# power_electronicsV4_1.net
KiCad netlist of a schematic drawn in EAGLE
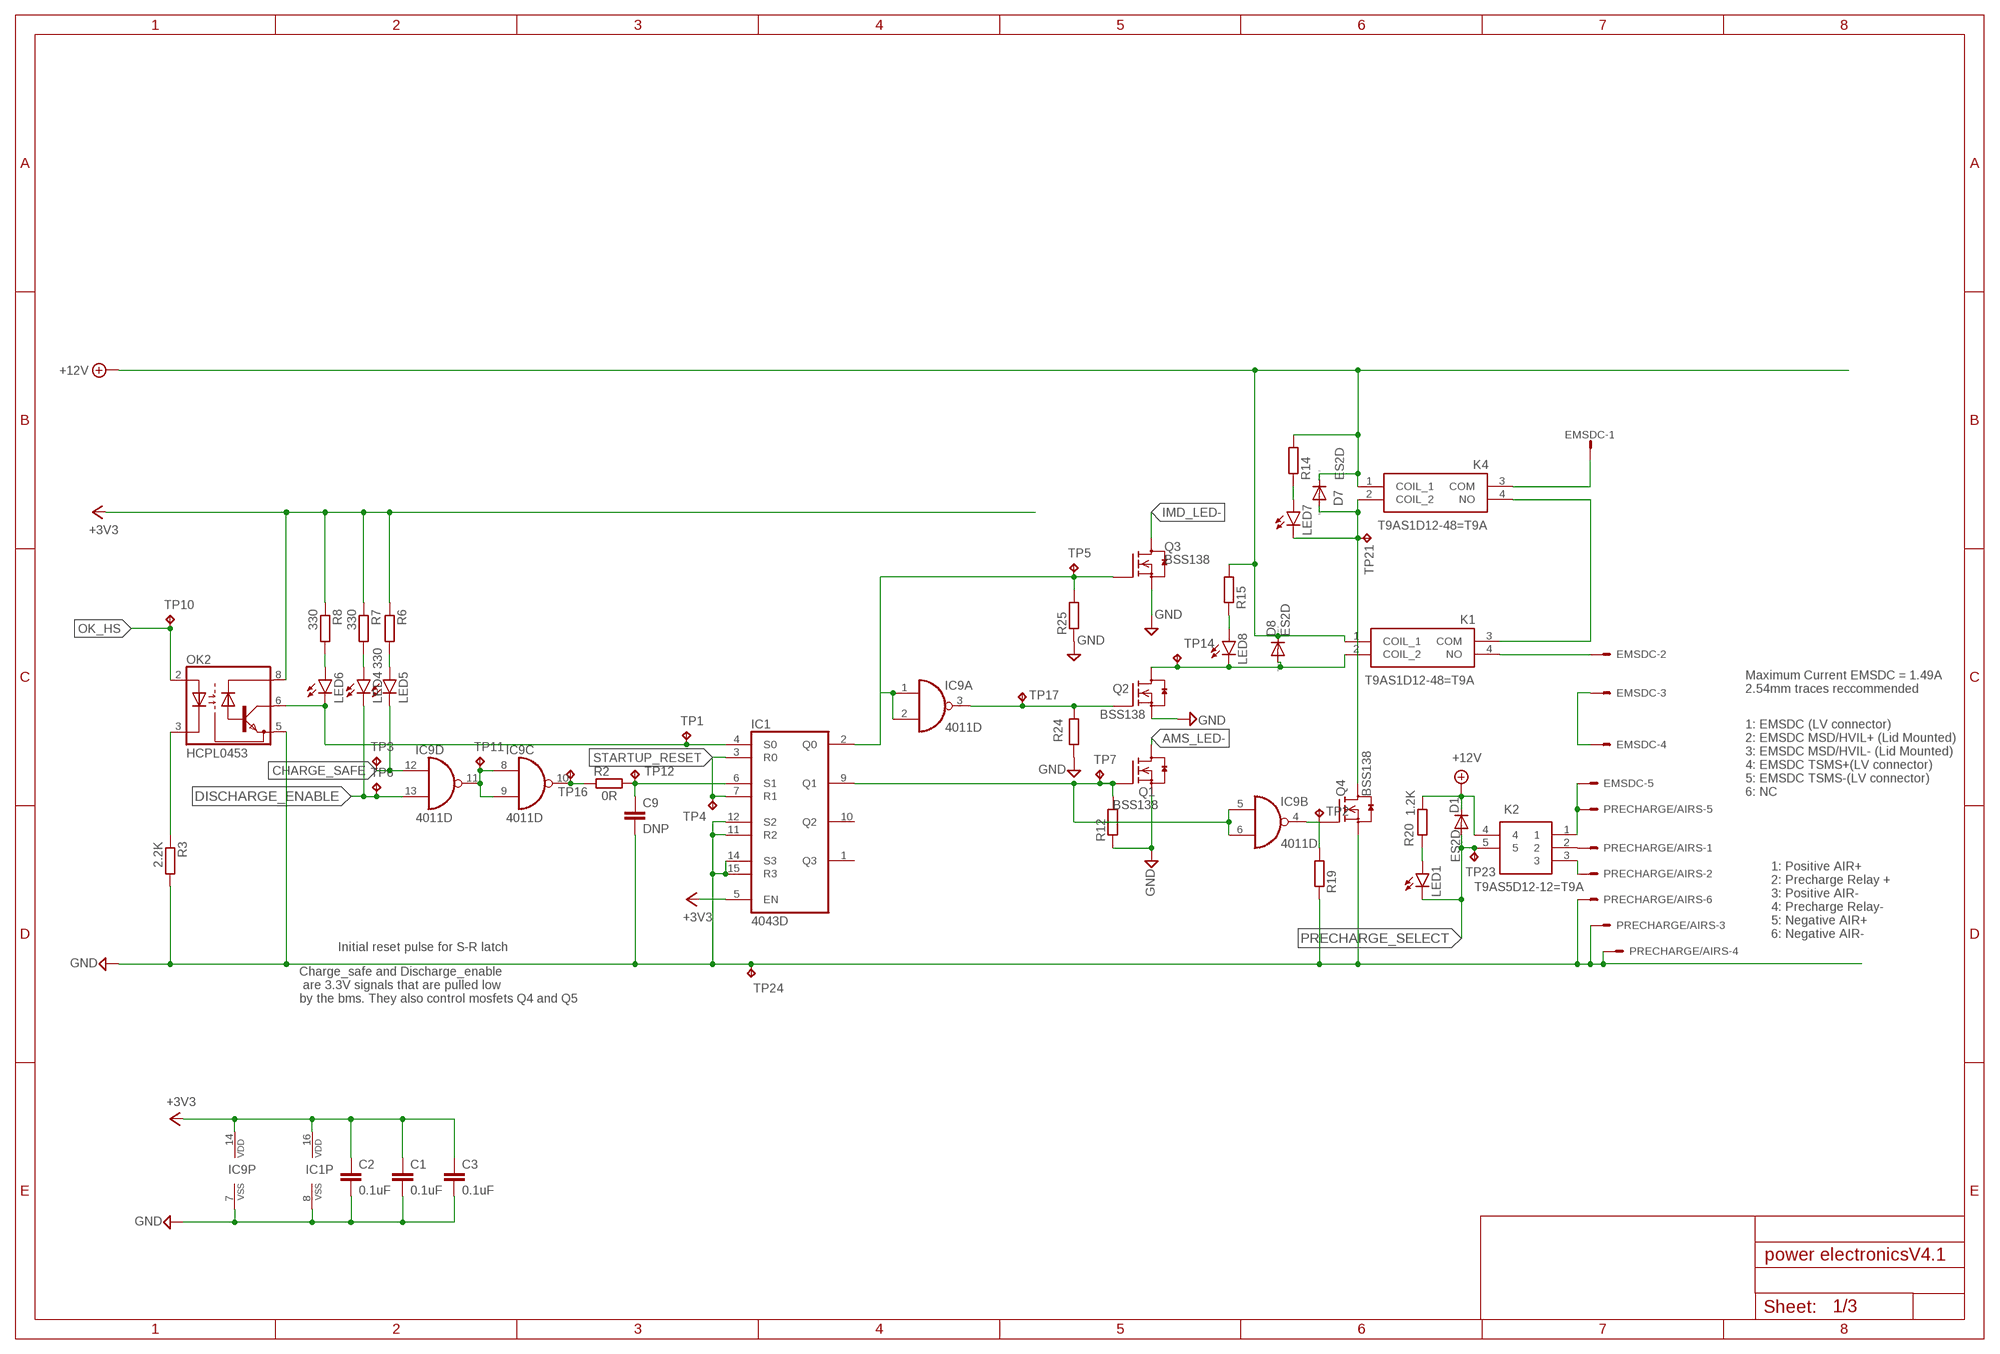
[diagram p0: schematic, sheet 1]
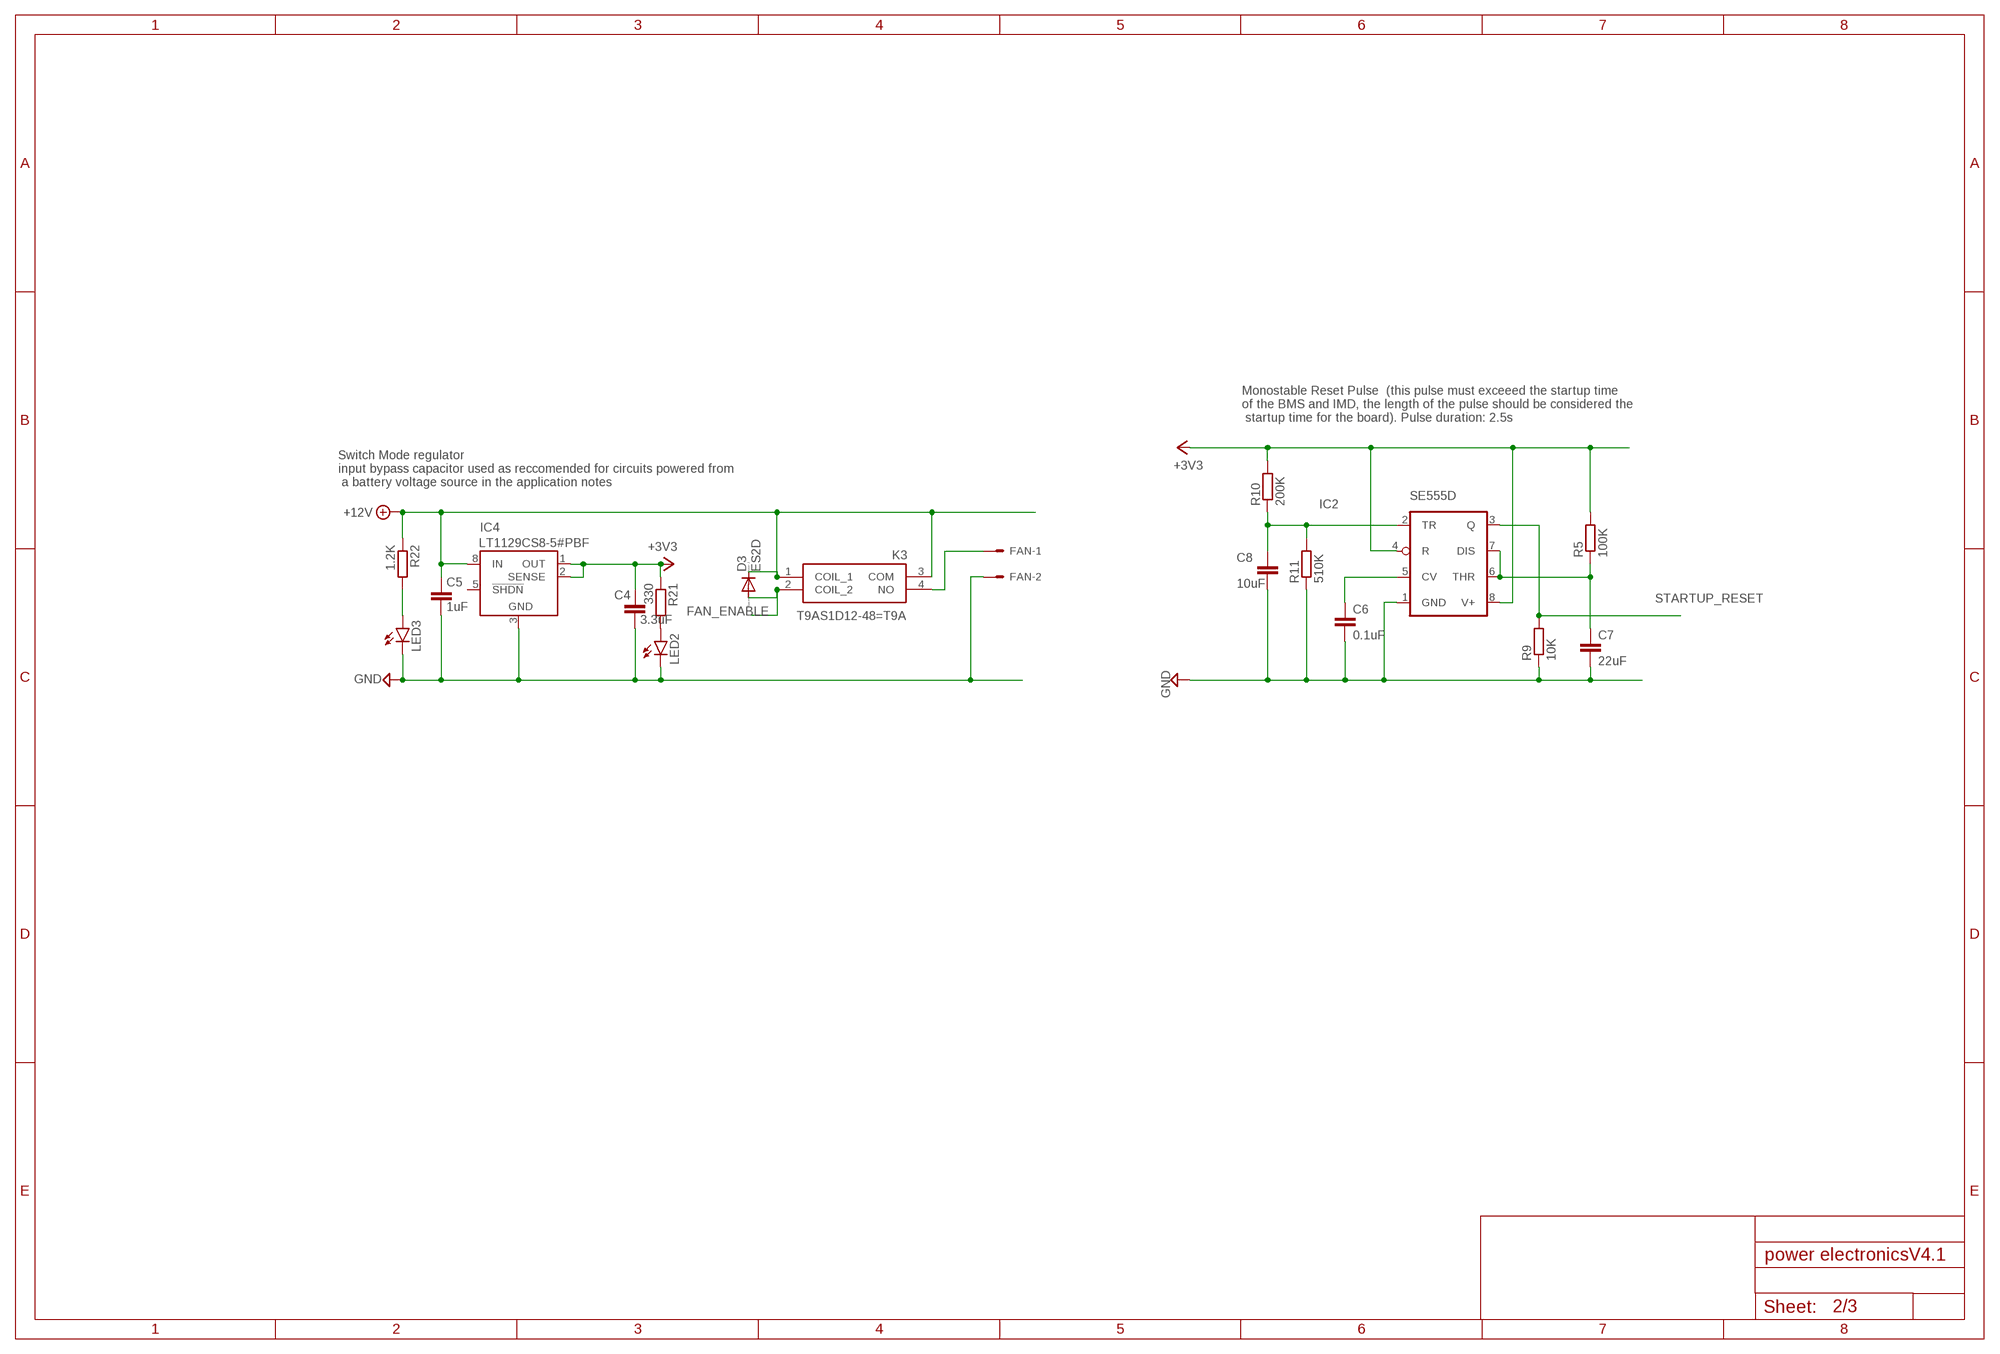
[diagram p1: schematic, sheet 2]
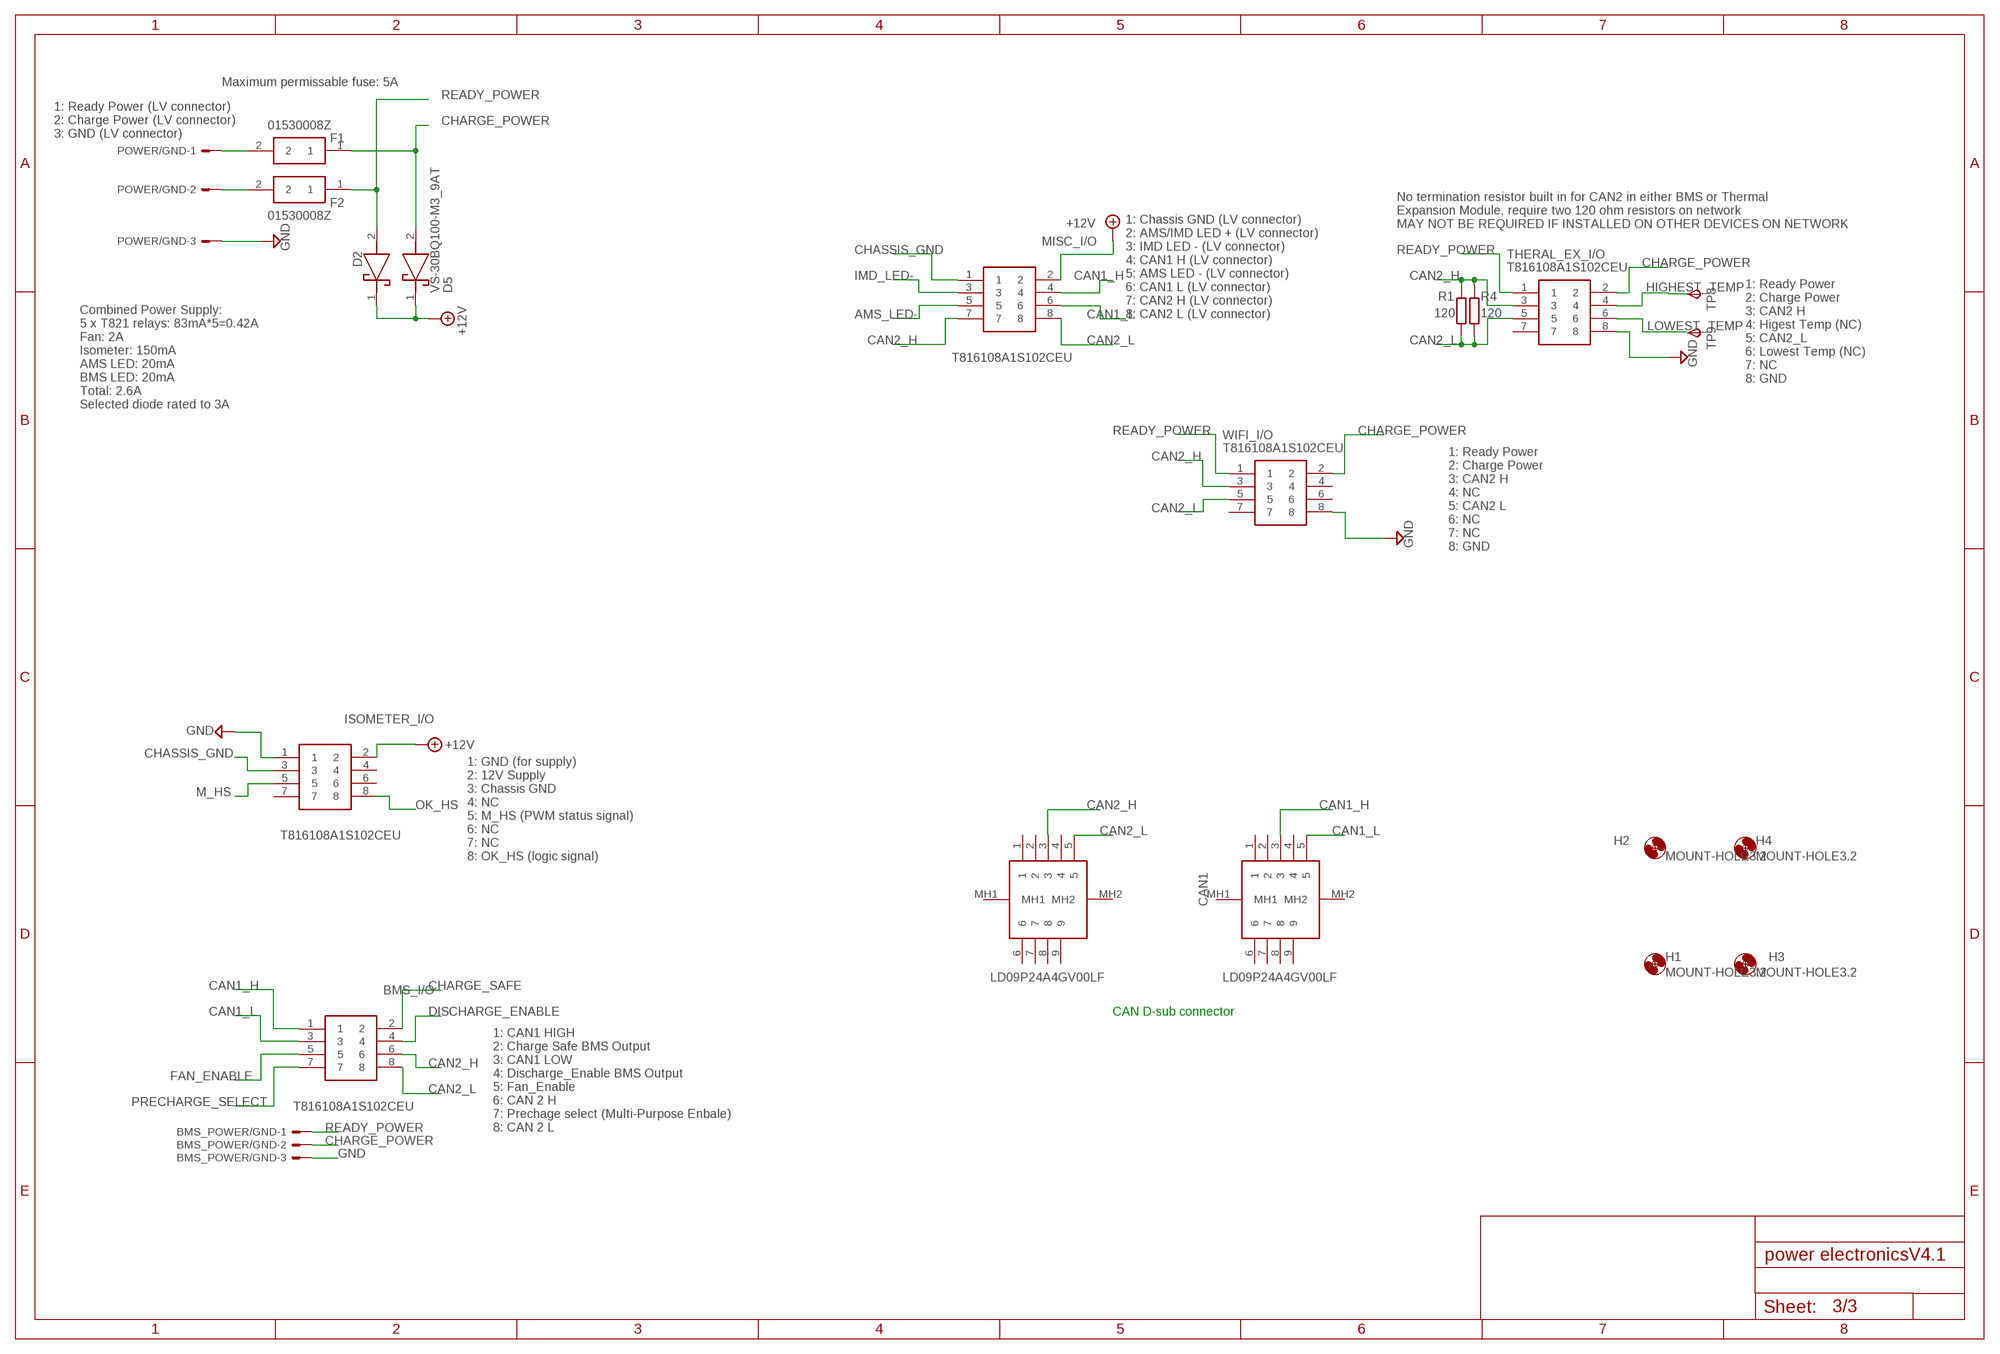
[diagram p2: schematic, sheet 3]

(export (version "E")
  (design (tool "Eeschema 10.0.6"))
  (components
    (comp (ref "C4")
      (value "3.3uF")
      (footprint "eagle-import:C0805")
      (libsource (lib "eagle-import") (part "C-EUC0805"))
    )
    (comp (ref "C5")
      (value "1uF")
      (footprint "eagle-import:C0805")
      (libsource (lib "eagle-import") (part "C-EUC0805"))
    )
    (comp (ref "C6")
      (value "0.1uF")
      (footprint "eagle-import:C0805")
      (libsource (lib "eagle-import") (part "C-EUC0805"))
    )
    (comp (ref "C7")
      (value "22uF")
      (footprint "eagle-import:C1206")
      (libsource (lib "eagle-import") (part "C-EUC1206"))
    )
    (comp (ref "C8")
      (value "10uF")
      (footprint "eagle-import:C0805")
      (libsource (lib "eagle-import") (part "C-EUC0805"))
    )
    (comp (ref "D3")
      (value "ES2D")
      (footprint "eagle-import:SMB")
      (libsource (lib "eagle-import") (part "ES2D"))
    )
    (comp (ref "FAN")
      (value "KK-156-2")
      (footprint "eagle-import:KK-156-2")
      (fields (field (name "MF") "MOLEX"))
      (libsource (lib "eagle-import") (part "KK-156-2"))
    )
    (comp (ref "IC2")
      (value "SE555D")
      (footprint "eagle-import:SO08")
      (libsource (lib "eagle-import") (part "555DSE"))
    )
    (comp (ref "IC4")
      (value "LT1129CS8")
      (footprint "eagle-import:SOIC8")
      (fields (field (name "MPN") "LT1129CS8-5#PBF"))
      (libsource (lib "eagle-import") (part "LT1129CS8"))
    )
    (comp (ref "K3")
      (value "T9AS1D12-48=T9A")
      (footprint "eagle-import:T9AS1D1248T9A")
      (fields (field (name "RS_PART_NUMBER") "6802534P"))
      (libsource (lib "eagle-import") (part "T9AS1D12-48=T9A"))
    )
    (comp (ref "LED2")
      (value "LEDSML0805")
      (footprint "eagle-import:SML0805")
      (libsource (lib "eagle-import") (part "LEDSML0805"))
    )
    (comp (ref "LED3")
      (value "LEDSML0805")
      (footprint "eagle-import:SML0805")
      (libsource (lib "eagle-import") (part "LEDSML0805"))
    )
    (comp (ref "R5")
      (value "100K")
      (footprint "eagle-import:R0805")
      (libsource (lib "eagle-import") (part "R-EU_R0805"))
    )
    (comp (ref "R9")
      (value "10K")
      (footprint "eagle-import:R0805")
      (libsource (lib "eagle-import") (part "R-EU_R0805"))
    )
    (comp (ref "R10")
      (value "200K")
      (footprint "eagle-import:R0805")
      (libsource (lib "eagle-import") (part "R-EU_R0805"))
    )
    (comp (ref "R11")
      (value "510K")
      (footprint "eagle-import:R0805")
      (libsource (lib "eagle-import") (part "R-EU_R0805"))
    )
    (comp (ref "R21")
      (value "330")
      (footprint "eagle-import:R0805")
      (libsource (lib "eagle-import") (part "R-EU_R0805"))
    )
    (comp (ref "R22")
      (value "1.2K")
      (footprint "eagle-import:R0805")
      (libsource (lib "eagle-import") (part "R-EU_R0805"))
    )
    (comp (ref "BMS_I/O")
      (value "T816108A1S102CEU")
      (footprint "eagle-import:T816108A1S102CEU")
      (libsource (lib "eagle-import") (part "T816108A1S102CEU"))
    )
    (comp (ref "BMS_POWER/GND")
      (value "KK-156-3")
      (footprint "eagle-import:KK-156-3")
      (fields (field (name "MF") "MOLEX"))
      (libsource (lib "eagle-import") (part "KK-156-3"))
    )
    (comp (ref "CAN1")
      (value "LD09P24A4GV00LF")
      (footprint "eagle-import:LD09P24A4GV00LF")
      (fields (field (name "MOUSER_PART_NUMBER") "649-LD09P24A4GV00LF"))
      (libsource (lib "eagle-import") (part "LD09P24A4GV00LF"))
    )
    (comp (ref "CAN2")
      (value "LD09P24A4GV00LF")
      (footprint "eagle-import:LD09P24A4GV00LF")
      (fields (field (name "MOUSER_PART_NUMBER") "649-LD09P24A4GV00LF"))
      (libsource (lib "eagle-import") (part "LD09P24A4GV00LF"))
    )
    (comp (ref "D2")
      (value "VS-30BQ100-M3_9AT")
      (footprint "eagle-import:DIOM7959X262N")
      (fields
        (field (name "MANUFACTURER_PART_NUMBER") "VS-30BQ100-M3/9AT")
        (field (name "MOUSER_PART_NUMBER") "78-VS-30BQ100-M39AT")
      )
      (libsource (lib "eagle-import") (part "VS-30BQ100-M3_9AT"))
    )
    (comp (ref "D5")
      (value "VS-30BQ100-M3_9AT")
      (footprint "eagle-import:DIOM7959X262N")
      (fields
        (field (name "MANUFACTURER_PART_NUMBER") "VS-30BQ100-M3/9AT")
        (field (name "MOUSER_PART_NUMBER") "78-VS-30BQ100-M39AT")
      )
      (libsource (lib "eagle-import") (part "VS-30BQ100-M3_9AT"))
    )
    (comp (ref "F1")
      (value "01530008Z")
      (footprint "eagle-import:01530008")
      (fields (field (name "RS_PART_NUMBER") "3607317"))
      (libsource (lib "eagle-import") (part "01530008Z"))
    )
    (comp (ref "F2")
      (value "01530008Z")
      (footprint "eagle-import:01530008")
      (fields (field (name "RS_PART_NUMBER") "3607317"))
      (libsource (lib "eagle-import") (part "01530008Z"))
    )
    (comp (ref "H1")
      (value "MOUNT-HOLE3.2")
      (footprint "eagle-import:3,2")
      (libsource (lib "eagle-import") (part "MOUNT-HOLE3.2"))
    )
    (comp (ref "H2")
      (value "MOUNT-HOLE3.2")
      (footprint "eagle-import:3,2")
      (libsource (lib "eagle-import") (part "MOUNT-HOLE3.2"))
    )
    (comp (ref "H3")
      (value "MOUNT-HOLE3.2")
      (footprint "eagle-import:3,2")
      (libsource (lib "eagle-import") (part "MOUNT-HOLE3.2"))
    )
    (comp (ref "H4")
      (value "MOUNT-HOLE3.2")
      (footprint "eagle-import:3,2")
      (libsource (lib "eagle-import") (part "MOUNT-HOLE3.2"))
    )
    (comp (ref "ISOMETER_I/O")
      (value "T816108A1S102CEU")
      (footprint "eagle-import:T816108A1S102CEU")
      (libsource (lib "eagle-import") (part "T816108A1S102CEU"))
    )
    (comp (ref "MISC_I/O")
      (value "T816108A1S102CEU")
      (footprint "eagle-import:T816108A1S102CEU")
      (libsource (lib "eagle-import") (part "T816108A1S102CEU"))
    )
    (comp (ref "POWER/GND")
      (value "KK-156-3")
      (footprint "eagle-import:KK-156-3")
      (fields (field (name "MF") "MOLEX"))
      (libsource (lib "eagle-import") (part "KK-156-3"))
    )
    (comp (ref "R1")
      (value "120")
      (footprint "eagle-import:R1206")
      (libsource (lib "eagle-import") (part "R-EU_R1206"))
    )
    (comp (ref "R4")
      (value "120")
      (footprint "eagle-import:R1206")
      (libsource (lib "eagle-import") (part "R-EU_R1206"))
    )
    (comp (ref "THERAL_EX_I/O")
      (value "T816108A1S102CEU")
      (footprint "eagle-import:T816108A1S102CEU")
      (libsource (lib "eagle-import") (part "T816108A1S102CEU"))
    )
    (comp (ref "TP8")
      (value "TPSTP11R")
      (footprint "eagle-import:TP11R")
      (libsource (lib "eagle-import") (part "TPSTP11R"))
    )
    (comp (ref "TP9")
      (value "TPSTP11R")
      (footprint "eagle-import:TP11R")
      (libsource (lib "eagle-import") (part "TPSTP11R"))
    )
    (comp (ref "WIFI_I/O")
      (value "T816108A1S102CEU")
      (footprint "eagle-import:T816108A1S102CEU")
      (libsource (lib "eagle-import") (part "T816108A1S102CEU"))
    )
    (comp (ref "C1")
      (value "0.1uF")
      (footprint "eagle-import:C0805")
      (libsource (lib "eagle-import") (part "C-EUC0805"))
    )
    (comp (ref "C2")
      (value "0.1uF")
      (footprint "eagle-import:C0805")
      (libsource (lib "eagle-import") (part "C-EUC0805"))
    )
    (comp (ref "C3")
      (value "0.1uF")
      (footprint "eagle-import:C0805")
      (libsource (lib "eagle-import") (part "C-EUC0805"))
    )
    (comp (ref "C9")
      (value "DNP")
      (footprint "eagle-import:C0805K")
      (libsource (lib "eagle-import") (part "C-EUC0805K"))
    )
    (comp (ref "D1")
      (value "ES2D")
      (footprint "eagle-import:SMB")
      (libsource (lib "eagle-import") (part "ES2D"))
    )
    (comp (ref "D7")
      (value "ES2D")
      (footprint "eagle-import:SMB")
      (libsource (lib "eagle-import") (part "ES2D"))
    )
    (comp (ref "D8")
      (value "ES2D")
      (footprint "eagle-import:SMB")
      (libsource (lib "eagle-import") (part "ES2D"))
    )
    (comp (ref "EMSDC")
      (value "KK-156-6")
      (footprint "eagle-import:KK-156-6")
      (fields (field (name "MF") "MOLEX"))
      (libsource (lib "eagle-import") (part "KK-156-6"))
    )
    (comp (ref "IC1")
      (value "4043D")
      (footprint "eagle-import:SO16")
      (libsource (lib "eagle-import") (part "4043D"))
    )
    (comp (ref "IC9")
      (value "4011D")
      (footprint "eagle-import:SO14")
      (libsource (lib "eagle-import") (part "4011D"))
    )
    (comp (ref "K1")
      (value "T9AS1D12-48=T9A")
      (footprint "eagle-import:T9AS1D1248T9A")
      (fields (field (name "RS_PART_NUMBER") "6802534P"))
      (libsource (lib "eagle-import") (part "T9AS1D12-48=T9A"))
    )
    (comp (ref "K2")
      (value "T9AS5D12-12=T9A")
      (footprint "eagle-import:T9AS1D12")
      (fields (field (name "RS_PART_NUMBER") "6802528"))
      (libsource (lib "eagle-import") (part "T9AS5D12-12=T9A"))
    )
    (comp (ref "K4")
      (value "T9AS1D12-48=T9A")
      (footprint "eagle-import:T9AS1D1248T9A")
      (fields (field (name "RS_PART_NUMBER") "6802534P"))
      (libsource (lib "eagle-import") (part "T9AS1D12-48=T9A"))
    )
    (comp (ref "LED1")
      (value "LEDSML0805")
      (footprint "eagle-import:SML0805")
      (libsource (lib "eagle-import") (part "LEDSML0805"))
    )
    (comp (ref "LED4")
      (value "LEDSML0805")
      (footprint "eagle-import:SML0805")
      (libsource (lib "eagle-import") (part "LEDSML0805"))
    )
    (comp (ref "LED5")
      (value "LEDSML0805")
      (footprint "eagle-import:SML0805")
      (libsource (lib "eagle-import") (part "LEDSML0805"))
    )
    (comp (ref "LED6")
      (value "LEDSML0805")
      (footprint "eagle-import:SML0805")
      (libsource (lib "eagle-import") (part "LEDSML0805"))
    )
    (comp (ref "LED7")
      (value "LEDSML0805")
      (footprint "eagle-import:SML0805")
      (libsource (lib "eagle-import") (part "LEDSML0805"))
    )
    (comp (ref "LED8")
      (value "LEDSML0805")
      (footprint "eagle-import:SML0805")
      (libsource (lib "eagle-import") (part "LEDSML0805"))
    )
    (comp (ref "OK2")
      (value "HCPL0453")
      (footprint "eagle-import:SOIC08")
      (fields (field (name "MF") "AGILENT TECHNOLOGIES") (field (name "MPN") "HCPL-0453-000E"))
      (libsource (lib "eagle-import") (part "HCPL0453"))
    )
    (comp (ref "PRECHARGE/AIRS")
      (value "KK-156-6")
      (footprint "eagle-import:KK-156-6")
      (fields (field (name "MF") "MOLEX"))
      (libsource (lib "eagle-import") (part "KK-156-6"))
    )
    (comp (ref "Q1")
      (value "BSS138")
      (footprint "eagle-import:SOT23")
      (libsource (lib "eagle-import") (part "BSS138"))
    )
    (comp (ref "Q2")
      (value "BSS138")
      (footprint "eagle-import:SOT23")
      (libsource (lib "eagle-import") (part "BSS138"))
    )
    (comp (ref "Q3")
      (value "BSS138")
      (footprint "eagle-import:SOT23")
      (libsource (lib "eagle-import") (part "BSS138"))
    )
    (comp (ref "Q4")
      (value "BSS138")
      (footprint "eagle-import:SOT23")
      (libsource (lib "eagle-import") (part "BSS138"))
    )
    (comp (ref "R2")
      (value "0R")
      (footprint "eagle-import:R0805")
      (libsource (lib "eagle-import") (part "R-EU_R0805"))
    )
    (comp (ref "R3")
      (value "2.2K")
      (footprint "eagle-import:R0805")
      (libsource (lib "eagle-import") (part "R-EU_R0805"))
    )
    (comp (ref "R6")
      (value "330")
      (footprint "eagle-import:R0805")
      (libsource (lib "eagle-import") (part "R-EU_R0805"))
    )
    (comp (ref "R7")
      (value "330")
      (footprint "eagle-import:R0805")
      (libsource (lib "eagle-import") (part "R-EU_R0805"))
    )
    (comp (ref "R8")
      (value "330")
      (footprint "eagle-import:R0805")
      (libsource (lib "eagle-import") (part "R-EU_R0805"))
    )
    (comp (ref "R12")
      (value "R-EU_R0805")
      (footprint "eagle-import:R0805")
      (libsource (lib "eagle-import") (part "R-EU_R0805"))
    )
    (comp (ref "R14")
      (value "R-EU_R0805")
      (footprint "eagle-import:R0805")
      (libsource (lib "eagle-import") (part "R-EU_R0805"))
    )
    (comp (ref "R15")
      (value "R-EU_R0805")
      (footprint "eagle-import:R0805")
      (libsource (lib "eagle-import") (part "R-EU_R0805"))
    )
    (comp (ref "R19")
      (value "R-EU_R0805")
      (footprint "eagle-import:R0805")
      (libsource (lib "eagle-import") (part "R-EU_R0805"))
    )
    (comp (ref "R20")
      (value "1.2K")
      (footprint "eagle-import:R0805")
      (libsource (lib "eagle-import") (part "R-EU_R0805"))
    )
    (comp (ref "R24")
      (value "R-EU_R0805")
      (footprint "eagle-import:R0805")
      (libsource (lib "eagle-import") (part "R-EU_R0805"))
    )
    (comp (ref "R25")
      (value "R-EU_R0805")
      (footprint "eagle-import:R0805")
      (libsource (lib "eagle-import") (part "R-EU_R0805"))
    )
    (comp (ref "TP1")
      (value "TPPAD1-17")
      (footprint "eagle-import:P1-17")
      (libsource (lib "eagle-import") (part "TPPAD1-17"))
    )
    (comp (ref "TP2")
      (value "TPPAD1-17")
      (footprint "eagle-import:P1-17")
      (libsource (lib "eagle-import") (part "TPPAD1-17"))
    )
    (comp (ref "TP3")
      (value "TPPAD1-17")
      (footprint "eagle-import:P1-17")
      (libsource (lib "eagle-import") (part "TPPAD1-17"))
    )
    (comp (ref "TP4")
      (value "TPPAD1-17")
      (footprint "eagle-import:P1-17")
      (libsource (lib "eagle-import") (part "TPPAD1-17"))
    )
    (comp (ref "TP5")
      (value "TPPAD1-17")
      (footprint "eagle-import:P1-17")
      (libsource (lib "eagle-import") (part "TPPAD1-17"))
    )
    (comp (ref "TP6")
      (value "TPPAD1-17")
      (footprint "eagle-import:P1-17")
      (libsource (lib "eagle-import") (part "TPPAD1-17"))
    )
    (comp (ref "TP7")
      (value "TPPAD1-17")
      (footprint "eagle-import:P1-17")
      (libsource (lib "eagle-import") (part "TPPAD1-17"))
    )
    (comp (ref "TP10")
      (value "TPPAD1-17")
      (footprint "eagle-import:P1-17")
      (libsource (lib "eagle-import") (part "TPPAD1-17"))
    )
    (comp (ref "TP11")
      (value "TPPAD1-17")
      (footprint "eagle-import:P1-17")
      (libsource (lib "eagle-import") (part "TPPAD1-17"))
    )
    (comp (ref "TP12")
      (value "TPPAD1-17")
      (footprint "eagle-import:P1-17")
      (libsource (lib "eagle-import") (part "TPPAD1-17"))
    )
    (comp (ref "TP14")
      (value "TPPAD1-17")
      (footprint "eagle-import:P1-17")
      (libsource (lib "eagle-import") (part "TPPAD1-17"))
    )
    (comp (ref "TP16")
      (value "TPPAD1-17")
      (footprint "eagle-import:P1-17")
      (libsource (lib "eagle-import") (part "TPPAD1-17"))
    )
    (comp (ref "TP17")
      (value "TPPAD1-17")
      (footprint "eagle-import:P1-17")
      (libsource (lib "eagle-import") (part "TPPAD1-17"))
    )
    (comp (ref "TP21")
      (value "TPPAD1-17")
      (footprint "eagle-import:P1-17")
      (libsource (lib "eagle-import") (part "TPPAD1-17"))
    )
    (comp (ref "TP23")
      (value "TPPAD1-17")
      (footprint "eagle-import:P1-17")
      (libsource (lib "eagle-import") (part "TPPAD1-17"))
    )
    (comp (ref "TP24")
      (value "TPPAD1-17")
      (footprint "eagle-import:P1-17")
      (libsource (lib "eagle-import") (part "TPPAD1-17"))
    )
  )
  (nets
    (net (code "1") (name "+3V3") (class "Default")
      (node (ref "C1") (pin "1") (pinfunction "1_1") (pintype "passive"))
      (node (ref "C2") (pin "1") (pinfunction "1_1") (pintype "passive"))
      (node (ref "C3") (pin "1") (pinfunction "1_1") (pintype "passive"))
      (node (ref "C4") (pin "1") (pinfunction "1_1") (pintype "passive"))
      (node (ref "IC1") (pin "16") (pinfunction "VDD_16") (pintype "power_in"))
      (node (ref "IC1") (pin "5") (pinfunction "EN_5") (pintype "input"))
      (node (ref "IC2") (pin "4") (pinfunction "R_4") (pintype "input"))
      (node (ref "IC2") (pin "8") (pinfunction "V+_8") (pintype "power_in"))
      (node (ref "IC4") (pin "1") (pinfunction "OUT_1") (pintype "output"))
      (node (ref "IC4") (pin "2") (pinfunction "SENSE_2") (pintype "input"))
      (node (ref "IC9") (pin "14") (pinfunction "VDD_14") (pintype "power_in"))
      (node (ref "OK2") (pin "8") (pinfunction "VCC_8") (pintype "passive"))
      (node (ref "R10") (pin "2") (pinfunction "2_2") (pintype "passive"))
      (node (ref "R21") (pin "1") (pinfunction "1_1") (pintype "passive"))
      (node (ref "R5") (pin "2") (pinfunction "2_2") (pintype "passive"))
      (node (ref "R6") (pin "1") (pinfunction "1_1") (pintype "passive"))
      (node (ref "R7") (pin "1") (pinfunction "1_1") (pintype "passive"))
      (node (ref "R8") (pin "1") (pinfunction "1_1") (pintype "passive"))
    )
    (net (code "2") (name "+12V") (class "Default")
      (node (ref "C5") (pin "1") (pinfunction "1_1") (pintype "passive"))
      (node (ref "D1") (pin "C") (pinfunction "C_C") (pintype "passive"))
      (node (ref "D2") (pin "1") (pinfunction "K_1") (pintype "bidirectional"))
      (node (ref "D3") (pin "C") (pinfunction "C_C") (pintype "passive"))
      (node (ref "D5") (pin "1") (pinfunction "K_1") (pintype "bidirectional"))
      (node (ref "D7") (pin "C") (pinfunction "C_C") (pintype "passive"))
      (node (ref "D8") (pin "C") (pinfunction "C_C") (pintype "passive"))
      (node (ref "IC4") (pin "8") (pinfunction "IN_8") (pintype "input"))
      (node (ref "ISOMETER_I/O") (pin "2") (pinfunction "2_2") (pintype "bidirectional"))
      (node (ref "K1") (pin "1") (pinfunction "COIL_1_1") (pintype "bidirectional"))
      (node (ref "K2") (pin "4") (pinfunction "4_4") (pintype "bidirectional"))
      (node (ref "K3") (pin "1") (pinfunction "COIL_1_1") (pintype "bidirectional"))
      (node (ref "K3") (pin "3") (pinfunction "COM_3") (pintype "bidirectional"))
      (node (ref "K4") (pin "1") (pinfunction "COIL_1_1") (pintype "bidirectional"))
      (node (ref "MISC_I/O") (pin "2") (pinfunction "2_2") (pintype "bidirectional"))
      (node (ref "R14") (pin "2") (pinfunction "2_2") (pintype "passive"))
      (node (ref "R15") (pin "2") (pinfunction "2_2") (pintype "passive"))
      (node (ref "R20") (pin "1") (pinfunction "1_1") (pintype "passive"))
      (node (ref "R22") (pin "1") (pinfunction "1_1") (pintype "passive"))
    )
    (net (code "3") (name "AMS_LED-") (class "Default")
      (node (ref "MISC_I/O") (pin "5") (pinfunction "5_5") (pintype "bidirectional"))
      (node (ref "Q1") (pin "3") (pinfunction "D_3") (pintype "passive"))
    )
    (net (code "4") (name "CAN1_H") (class "Default")
      (node (ref "BMS_I/O") (pin "1") (pinfunction "1_1") (pintype "bidirectional"))
      (node (ref "CAN1") (pin "3") (pinfunction "3_3") (pintype "bidirectional"))
      (node (ref "MISC_I/O") (pin "4") (pinfunction "4_4") (pintype "bidirectional"))
    )
    (net (code "5") (name "CAN1_L") (class "Default")
      (node (ref "BMS_I/O") (pin "3") (pinfunction "3_3") (pintype "bidirectional"))
      (node (ref "CAN1") (pin "5") (pinfunction "5_5") (pintype "bidirectional"))
      (node (ref "MISC_I/O") (pin "6") (pinfunction "6_6") (pintype "bidirectional"))
    )
    (net (code "6") (name "CAN2_H") (class "Default")
      (node (ref "BMS_I/O") (pin "6") (pinfunction "6_6") (pintype "bidirectional"))
      (node (ref "CAN2") (pin "3") (pinfunction "3_3") (pintype "bidirectional"))
      (node (ref "MISC_I/O") (pin "7") (pinfunction "7_7") (pintype "bidirectional"))
      (node (ref "R1") (pin "1") (pinfunction "1_1") (pintype "passive"))
      (node (ref "R4") (pin "1") (pinfunction "1_1") (pintype "passive"))
      (node (ref "THERAL_EX_I/O") (pin "3") (pinfunction "3_3") (pintype "bidirectional"))
      (node (ref "WIFI_I/O") (pin "3") (pinfunction "3_3") (pintype "bidirectional"))
    )
    (net (code "7") (name "CAN2_L") (class "Default")
      (node (ref "BMS_I/O") (pin "8") (pinfunction "8_8") (pintype "bidirectional"))
      (node (ref "CAN2") (pin "5") (pinfunction "5_5") (pintype "bidirectional"))
      (node (ref "MISC_I/O") (pin "8") (pinfunction "8_8") (pintype "bidirectional"))
      (node (ref "R1") (pin "2") (pinfunction "2_2") (pintype "passive"))
      (node (ref "R4") (pin "2") (pinfunction "2_2") (pintype "passive"))
      (node (ref "THERAL_EX_I/O") (pin "5") (pinfunction "5_5") (pintype "bidirectional"))
      (node (ref "WIFI_I/O") (pin "5") (pinfunction "5_5") (pintype "bidirectional"))
    )
    (net (code "8") (name "CHARGE_POWER") (class "Default")
      (node (ref "BMS_POWER/GND") (pin "2") (pinfunction "S_2") (pintype "passive"))
      (node (ref "D5") (pin "2") (pinfunction "A_2") (pintype "bidirectional"))
      (node (ref "F1") (pin "1") (pinfunction "1_1") (pintype "bidirectional"))
      (node (ref "THERAL_EX_I/O") (pin "2") (pinfunction "2_2") (pintype "bidirectional"))
      (node (ref "WIFI_I/O") (pin "2") (pinfunction "2_2") (pintype "bidirectional"))
    )
    (net (code "9") (name "CHARGE_SAFE") (class "Default")
      (node (ref "BMS_I/O") (pin "2") (pinfunction "2_2") (pintype "bidirectional"))
      (node (ref "IC9") (pin "12") (pinfunction "I0_12") (pintype "input"))
      (node (ref "LED5") (pin "C") (pinfunction "C_C") (pintype "passive"))
      (node (ref "TP3") (pin "TP") (pinfunction "TP_TP") (pintype "input"))
    )
    (net (code "10") (name "CHASSIS_GND") (class "Default")
      (node (ref "ISOMETER_I/O") (pin "3") (pinfunction "3_3") (pintype "bidirectional"))
      (node (ref "MISC_I/O") (pin "1") (pinfunction "1_1") (pintype "bidirectional"))
    )
    (net (code "11") (name "DISCHARGE_ENABLE") (class "Default")
      (node (ref "BMS_I/O") (pin "4") (pinfunction "4_4") (pintype "bidirectional"))
      (node (ref "IC1") (pin "9") (pinfunction "Q1_9") (pintype "output"))
      (node (ref "IC9") (pin "13") (pinfunction "I1_13") (pintype "input"))
      (node (ref "IC9") (pin "5") (pinfunction "I0_5") (pintype "input"))
      (node (ref "IC9") (pin "6") (pinfunction "I1_6") (pintype "input"))
      (node (ref "LED4") (pin "C") (pinfunction "C_C") (pintype "passive"))
      (node (ref "Q1") (pin "1") (pinfunction "G_1") (pintype "passive"))
      (node (ref "R12") (pin "2") (pinfunction "2_2") (pintype "passive"))
      (node (ref "TP6") (pin "TP") (pinfunction "TP_TP") (pintype "input"))
      (node (ref "TP7") (pin "TP") (pinfunction "TP_TP") (pintype "input"))
    )
    (net (code "12") (name "FAN_ENABLE") (class "Default")
      (node (ref "BMS_I/O") (pin "5") (pinfunction "5_5") (pintype "bidirectional"))
      (node (ref "D3") (pin "A") (pinfunction "A_A") (pintype "passive"))
      (node (ref "K3") (pin "2") (pinfunction "COIL_2_2") (pintype "bidirectional"))
    )
    (net (code "13") (name "GND") (class "Default")
      (node (ref "BMS_POWER/GND") (pin "3") (pinfunction "S_3") (pintype "passive"))
      (node (ref "C1") (pin "2") (pinfunction "2_2") (pintype "passive"))
      (node (ref "C2") (pin "2") (pinfunction "2_2") (pintype "passive"))
      (node (ref "C3") (pin "2") (pinfunction "2_2") (pintype "passive"))
      (node (ref "C4") (pin "2") (pinfunction "2_2") (pintype "passive"))
      (node (ref "C5") (pin "2") (pinfunction "2_2") (pintype "passive"))
      (node (ref "C6") (pin "2") (pinfunction "2_2") (pintype "passive"))
      (node (ref "C7") (pin "2") (pinfunction "2_2") (pintype "passive"))
      (node (ref "C8") (pin "2") (pinfunction "2_2") (pintype "passive"))
      (node (ref "C9") (pin "2") (pinfunction "2_2") (pintype "passive"))
      (node (ref "FAN") (pin "2") (pinfunction "S_2") (pintype "passive"))
      (node (ref "IC1") (pin "11") (pinfunction "R2_11") (pintype "input"))
      (node (ref "IC1") (pin "12") (pinfunction "S2_12") (pintype "input"))
      (node (ref "IC1") (pin "14") (pinfunction "S3_14") (pintype "input"))
      (node (ref "IC1") (pin "15") (pinfunction "R3_15") (pintype "input"))
      (node (ref "IC1") (pin "8") (pinfunction "VSS_8") (pintype "power_in"))
      (node (ref "IC2") (pin "1") (pinfunction "GND_1") (pintype "power_in"))
      (node (ref "IC4") (pin "3") (pinfunction "GND_3") (pintype "power_in"))
      (node (ref "IC9") (pin "7") (pinfunction "VSS_7") (pintype "power_in"))
      (node (ref "ISOMETER_I/O") (pin "1") (pinfunction "1_1") (pintype "bidirectional"))
      (node (ref "LED2") (pin "C") (pinfunction "C_C") (pintype "passive"))
      (node (ref "LED3") (pin "C") (pinfunction "C_C") (pintype "passive"))
      (node (ref "OK2") (pin "5") (pinfunction "GND_5") (pintype "passive"))
      (node (ref "POWER/GND") (pin "3") (pinfunction "S_3") (pintype "passive"))
      (node (ref "PRECHARGE/AIRS") (pin "3") (pinfunction "S_3") (pintype "passive"))
      (node (ref "PRECHARGE/AIRS") (pin "4") (pinfunction "S_4") (pintype "passive"))
      (node (ref "PRECHARGE/AIRS") (pin "6") (pinfunction "S_6") (pintype "passive"))
      (node (ref "Q1") (pin "2") (pinfunction "S_2") (pintype "passive"))
      (node (ref "Q2") (pin "2") (pinfunction "S_2") (pintype "passive"))
      (node (ref "Q3") (pin "2") (pinfunction "S_2") (pintype "passive"))
      (node (ref "Q4") (pin "2") (pinfunction "S_2") (pintype "passive"))
      (node (ref "R11") (pin "1") (pinfunction "1_1") (pintype "passive"))
      (node (ref "R12") (pin "1") (pinfunction "1_1") (pintype "passive"))
      (node (ref "R19") (pin "1") (pinfunction "1_1") (pintype "passive"))
      (node (ref "R24") (pin "1") (pinfunction "1_1") (pintype "passive"))
      (node (ref "R25") (pin "1") (pinfunction "1_1") (pintype "passive"))
      (node (ref "R3") (pin "2") (pinfunction "2_2") (pintype "passive"))
      (node (ref "R9") (pin "1") (pinfunction "1_1") (pintype "passive"))
      (node (ref "THERAL_EX_I/O") (pin "8") (pinfunction "8_8") (pintype "bidirectional"))
      (node (ref "TP24") (pin "TP") (pinfunction "TP_TP") (pintype "input"))
      (node (ref "WIFI_I/O") (pin "8") (pinfunction "8_8") (pintype "bidirectional"))
    )
    (net (code "14") (name "HIGHEST_TEMP") (class "Default")
      (node (ref "THERAL_EX_I/O") (pin "4") (pinfunction "4_4") (pintype "bidirectional"))
      (node (ref "TP8") (pin "TP") (pinfunction "PP_TP") (pintype "input"))
    )
    (net (code "15") (name "IMD_LED-") (class "Default")
      (node (ref "MISC_I/O") (pin "3") (pinfunction "3_3") (pintype "bidirectional"))
      (node (ref "Q3") (pin "3") (pinfunction "D_3") (pintype "passive"))
    )
    (net (code "16") (name "LOWEST_TEMP") (class "Default")
      (node (ref "THERAL_EX_I/O") (pin "6") (pinfunction "6_6") (pintype "bidirectional"))
      (node (ref "TP9") (pin "TP") (pinfunction "PP_TP") (pintype "input"))
    )
    (net (code "17") (name "M_HS") (class "Default")
      (node (ref "ISOMETER_I/O") (pin "5") (pinfunction "5_5") (pintype "bidirectional"))
    )
    (net (code "18") (name "Net-(EMSDCA-S)") (class "Default")
      (node (ref "EMSDC") (pin "1") (pinfunction "S_1") (pintype "passive"))
      (node (ref "K4") (pin "3") (pinfunction "COM_3") (pintype "bidirectional"))
    )
    (net (code "19") (name "Net-(EMSDCB-S)") (class "Default")
      (node (ref "EMSDC") (pin "2") (pinfunction "S_2") (pintype "passive"))
      (node (ref "K1") (pin "4") (pinfunction "NO_4") (pintype "bidirectional"))
    )
    (net (code "20") (name "Net-(EMSDCC-S)") (class "Default")
      (node (ref "EMSDC") (pin "3") (pinfunction "S_3") (pintype "passive"))
      (node (ref "EMSDC") (pin "4") (pinfunction "S_4") (pintype "passive"))
    )
    (net (code "21") (name "Net-(EMSDCE-S)") (class "Default")
      (node (ref "EMSDC") (pin "5") (pinfunction "S_5") (pintype "passive"))
      (node (ref "K2") (pin "1") (pinfunction "1_1") (pintype "bidirectional"))
      (node (ref "PRECHARGE/AIRS") (pin "5") (pinfunction "S_5") (pintype "passive"))
    )
    (net (code "22") (name "Net-(FANA-S)") (class "Default")
      (node (ref "FAN") (pin "1") (pinfunction "S_1") (pintype "passive"))
      (node (ref "K3") (pin "4") (pinfunction "NO_4") (pintype "bidirectional"))
    )
    (net (code "23") (name "Net-(IC1A-Q0)") (class "Default")
      (node (ref "IC1") (pin "2") (pinfunction "Q0_2") (pintype "output"))
      (node (ref "IC9") (pin "1") (pinfunction "I0_1") (pintype "input"))
      (node (ref "IC9") (pin "2") (pinfunction "I1_2") (pintype "input"))
      (node (ref "Q3") (pin "1") (pinfunction "G_1") (pintype "passive"))
      (node (ref "R25") (pin "2") (pinfunction "2_2") (pintype "passive"))
      (node (ref "TP5") (pin "TP") (pinfunction "TP_TP") (pintype "input"))
    )
    (net (code "24") (name "Net-(IC1A-S0)") (class "Default")
      (node (ref "IC1") (pin "4") (pinfunction "S0_4") (pintype "input"))
      (node (ref "LED6") (pin "C") (pinfunction "C_C") (pintype "passive"))
      (node (ref "OK2") (pin "6") (pinfunction "VO_6") (pintype "passive"))
      (node (ref "TP1") (pin "TP") (pinfunction "TP_TP") (pintype "input"))
    )
    (net (code "25") (name "Net-(IC1A-S1)") (class "Default")
      (node (ref "C9") (pin "1") (pinfunction "1_1") (pintype "passive"))
      (node (ref "IC1") (pin "6") (pinfunction "S1_6") (pintype "input"))
      (node (ref "R2") (pin "2") (pinfunction "2_2") (pintype "passive"))
      (node (ref "TP12") (pin "TP") (pinfunction "TP_TP") (pintype "input"))
    )
    (net (code "26") (name "Net-(IC2-CV)") (class "Default")
      (node (ref "C6") (pin "1") (pinfunction "1_1") (pintype "passive"))
      (node (ref "IC2") (pin "5") (pinfunction "CV_5") (pintype "input"))
    )
    (net (code "27") (name "Net-(IC2-DIS)") (class "Default")
      (node (ref "C7") (pin "1") (pinfunction "1_1") (pintype "passive"))
      (node (ref "IC2") (pin "6") (pinfunction "THR_6") (pintype "input"))
      (node (ref "IC2") (pin "7") (pinfunction "DIS_7") (pintype "input"))
      (node (ref "R5") (pin "1") (pinfunction "1_1") (pintype "passive"))
    )
    (net (code "28") (name "Net-(IC2-TR)") (class "Default")
      (node (ref "C8") (pin "1") (pinfunction "1_1") (pintype "passive"))
      (node (ref "IC2") (pin "2") (pinfunction "TR_2") (pintype "input"))
      (node (ref "R10") (pin "1") (pinfunction "1_1") (pintype "passive"))
      (node (ref "R11") (pin "2") (pinfunction "2_2") (pintype "passive"))
    )
    (net (code "29") (name "Net-(IC9A-O)") (class "Default")
      (node (ref "IC9") (pin "3") (pinfunction "O_3") (pintype "output"))
      (node (ref "Q2") (pin "1") (pinfunction "G_1") (pintype "passive"))
      (node (ref "R24") (pin "2") (pinfunction "2_2") (pintype "passive"))
      (node (ref "TP17") (pin "TP") (pinfunction "TP_TP") (pintype "input"))
    )
    (net (code "30") (name "Net-(IC9B-O)") (class "Default")
      (node (ref "IC9") (pin "4") (pinfunction "O_4") (pintype "output"))
      (node (ref "Q4") (pin "1") (pinfunction "G_1") (pintype "passive"))
      (node (ref "R19") (pin "2") (pinfunction "2_2") (pintype "passive"))
      (node (ref "TP2") (pin "TP") (pinfunction "TP_TP") (pintype "input"))
    )
    (net (code "31") (name "Net-(IC9C-I0)") (class "Default")
      (node (ref "IC9") (pin "11") (pinfunction "O_11") (pintype "output"))
      (node (ref "IC9") (pin "8") (pinfunction "I0_8") (pintype "input"))
      (node (ref "IC9") (pin "9") (pinfunction "I1_9") (pintype "input"))
      (node (ref "TP11") (pin "TP") (pinfunction "TP_TP") (pintype "input"))
    )
    (net (code "32") (name "Net-(IC9C-O)") (class "Default")
      (node (ref "IC9") (pin "10") (pinfunction "O_10") (pintype "output"))
      (node (ref "R2") (pin "1") (pinfunction "1_1") (pintype "passive"))
      (node (ref "TP16") (pin "TP") (pinfunction "TP_TP") (pintype "input"))
    )
    (net (code "33") (name "Net-(K1-COIL_2)") (class "Default")
      (node (ref "D8") (pin "A") (pinfunction "A_A") (pintype "passive"))
      (node (ref "K1") (pin "2") (pinfunction "COIL_2_2") (pintype "bidirectional"))
      (node (ref "LED8") (pin "C") (pinfunction "C_C") (pintype "passive"))
      (node (ref "Q2") (pin "3") (pinfunction "D_3") (pintype "passive"))
      (node (ref "TP14") (pin "TP") (pinfunction "TP_TP") (pintype "input"))
    )
    (net (code "34") (name "Net-(K1-COM)") (class "Default")
      (node (ref "K1") (pin "3") (pinfunction "COM_3") (pintype "bidirectional"))
      (node (ref "K4") (pin "4") (pinfunction "NO_4") (pintype "bidirectional"))
    )
    (net (code "35") (name "Net-(K4-COIL_2)") (class "Default")
      (node (ref "D7") (pin "A") (pinfunction "A_A") (pintype "passive"))
      (node (ref "K4") (pin "2") (pinfunction "COIL_2_2") (pintype "bidirectional"))
      (node (ref "LED7") (pin "C") (pinfunction "C_C") (pintype "passive"))
      (node (ref "Q4") (pin "3") (pinfunction "D_3") (pintype "passive"))
      (node (ref "TP21") (pin "TP") (pinfunction "TP_TP") (pintype "input"))
    )
    (net (code "36") (name "Net-(LED1-PadA)") (class "Default")
      (node (ref "LED1") (pin "A") (pinfunction "A_A") (pintype "passive"))
      (node (ref "R20") (pin "2") (pinfunction "2_2") (pintype "passive"))
    )
    (net (code "37") (name "Net-(LED2-PadA)") (class "Default")
      (node (ref "LED2") (pin "A") (pinfunction "A_A") (pintype "passive"))
      (node (ref "R21") (pin "2") (pinfunction "2_2") (pintype "passive"))
    )
    (net (code "38") (name "Net-(LED3-PadA)") (class "Default")
      (node (ref "LED3") (pin "A") (pinfunction "A_A") (pintype "passive"))
      (node (ref "R22") (pin "2") (pinfunction "2_2") (pintype "passive"))
    )
    (net (code "39") (name "Net-(LED4-PadA)") (class "Default")
      (node (ref "LED4") (pin "A") (pinfunction "A_A") (pintype "passive"))
      (node (ref "R7") (pin "2") (pinfunction "2_2") (pintype "passive"))
    )
    (net (code "40") (name "Net-(LED5-PadA)") (class "Default")
      (node (ref "LED5") (pin "A") (pinfunction "A_A") (pintype "passive"))
      (node (ref "R6") (pin "2") (pinfunction "2_2") (pintype "passive"))
    )
    (net (code "41") (name "Net-(LED6-PadA)") (class "Default")
      (node (ref "LED6") (pin "A") (pinfunction "A_A") (pintype "passive"))
      (node (ref "R8") (pin "2") (pinfunction "2_2") (pintype "passive"))
    )
    (net (code "42") (name "Net-(LED7-PadA)") (class "Default")
      (node (ref "LED7") (pin "A") (pinfunction "A_A") (pintype "passive"))
      (node (ref "R14") (pin "1") (pinfunction "1_1") (pintype "passive"))
    )
    (net (code "43") (name "Net-(LED8-PadA)") (class "Default")
      (node (ref "LED8") (pin "A") (pinfunction "A_A") (pintype "passive"))
      (node (ref "R15") (pin "1") (pinfunction "1_1") (pintype "passive"))
    )
    (net (code "44") (name "Net-(OK2-C)") (class "Default")
      (node (ref "OK2") (pin "3") (pinfunction "C_3") (pintype "passive"))
      (node (ref "R3") (pin "1") (pinfunction "1_1") (pintype "passive"))
    )
    (net (code "45") (name "Net-(POWER/GNDA-S)") (class "Default")
      (node (ref "F1") (pin "2") (pinfunction "2_2") (pintype "bidirectional"))
      (node (ref "POWER/GND") (pin "1") (pinfunction "S_1") (pintype "passive"))
    )
    (net (code "46") (name "Net-(POWER/GNDB-S)") (class "Default")
      (node (ref "F2") (pin "2") (pinfunction "2_2") (pintype "bidirectional"))
      (node (ref "POWER/GND") (pin "2") (pinfunction "S_2") (pintype "passive"))
    )
    (net (code "47") (name "Net-(PRECHARGE/AIRSA-S)") (class "Default")
      (node (ref "K2") (pin "2") (pinfunction "2_2") (pintype "bidirectional"))
      (node (ref "PRECHARGE/AIRS") (pin "1") (pinfunction "S_1") (pintype "passive"))
    )
    (net (code "48") (name "Net-(PRECHARGE/AIRSB-S)") (class "Default")
      (node (ref "K2") (pin "3") (pinfunction "3_3") (pintype "bidirectional"))
      (node (ref "PRECHARGE/AIRS") (pin "2") (pinfunction "S_2") (pintype "passive"))
    )
    (net (code "49") (name "OK_HS") (class "Default")
      (node (ref "ISOMETER_I/O") (pin "8") (pinfunction "8_8") (pintype "bidirectional"))
      (node (ref "OK2") (pin "2") (pinfunction "A_2") (pintype "passive"))
      (node (ref "TP10") (pin "TP") (pinfunction "TP_TP") (pintype "input"))
    )
    (net (code "50") (name "PRECHARGE_SELECT") (class "Default")
      (node (ref "BMS_I/O") (pin "7") (pinfunction "7_7") (pintype "bidirectional"))
      (node (ref "D1") (pin "A") (pinfunction "A_A") (pintype "passive"))
      (node (ref "K2") (pin "5") (pinfunction "5_5") (pintype "bidirectional"))
      (node (ref "LED1") (pin "C") (pinfunction "C_C") (pintype "passive"))
      (node (ref "TP23") (pin "TP") (pinfunction "TP_TP") (pintype "input"))
    )
    (net (code "51") (name "READY_POWER") (class "Default")
      (node (ref "BMS_POWER/GND") (pin "1") (pinfunction "S_1") (pintype "passive"))
      (node (ref "D2") (pin "2") (pinfunction "A_2") (pintype "bidirectional"))
      (node (ref "F2") (pin "1") (pinfunction "1_1") (pintype "bidirectional"))
      (node (ref "THERAL_EX_I/O") (pin "1") (pinfunction "1_1") (pintype "bidirectional"))
      (node (ref "WIFI_I/O") (pin "1") (pinfunction "1_1") (pintype "bidirectional"))
    )
    (net (code "52") (name "STARTUP_RESET") (class "Default")
      (node (ref "IC1") (pin "3") (pinfunction "R0_3") (pintype "input"))
      (node (ref "IC1") (pin "7") (pinfunction "R1_7") (pintype "input"))
      (node (ref "IC2") (pin "3") (pinfunction "Q_3") (pintype "output"))
      (node (ref "R9") (pin "2") (pinfunction "2_2") (pintype "passive"))
      (node (ref "TP4") (pin "TP") (pinfunction "TP_TP") (pintype "input"))
    )
    (net (code "53") (name "unconnected-(CAN1-Pad1)") (class "Default")
      (node (ref "CAN1") (pin "1") (pinfunction "1_1") (pintype "bidirectional"))
    )
    (net (code "54") (name "unconnected-(CAN1-Pad2)") (class "Default")
      (node (ref "CAN1") (pin "2") (pinfunction "2_2") (pintype "bidirectional"))
    )
    (net (code "55") (name "unconnected-(CAN1-Pad4)") (class "Default")
      (node (ref "CAN1") (pin "4") (pinfunction "4_4") (pintype "bidirectional"))
    )
    (net (code "56") (name "unconnected-(CAN1-Pad6)") (class "Default")
      (node (ref "CAN1") (pin "6") (pinfunction "6_6") (pintype "bidirectional"))
    )
    (net (code "57") (name "unconnected-(CAN1-Pad7)") (class "Default")
      (node (ref "CAN1") (pin "7") (pinfunction "7_7") (pintype "bidirectional"))
    )
    (net (code "58") (name "unconnected-(CAN1-Pad8)") (class "Default")
      (node (ref "CAN1") (pin "8") (pinfunction "8_8") (pintype "bidirectional"))
    )
    (net (code "59") (name "unconnected-(CAN1-Pad9)") (class "Default")
      (node (ref "CAN1") (pin "9") (pinfunction "9_9") (pintype "bidirectional"))
    )
    (net (code "60") (name "unconnected-(CAN1-PadMH1)") (class "Default")
      (node (ref "CAN1") (pin "MH1") (pinfunction "MH1_MH1") (pintype "bidirectional"))
    )
    (net (code "61") (name "unconnected-(CAN1-PadMH2)") (class "Default")
      (node (ref "CAN1") (pin "MH2") (pinfunction "MH2_MH2") (pintype "bidirectional"))
    )
    (net (code "62") (name "unconnected-(CAN2-Pad1)") (class "Default")
      (node (ref "CAN2") (pin "1") (pinfunction "1_1") (pintype "bidirectional"))
    )
    (net (code "63") (name "unconnected-(CAN2-Pad2)") (class "Default")
      (node (ref "CAN2") (pin "2") (pinfunction "2_2") (pintype "bidirectional"))
    )
    (net (code "64") (name "unconnected-(CAN2-Pad4)") (class "Default")
      (node (ref "CAN2") (pin "4") (pinfunction "4_4") (pintype "bidirectional"))
    )
    (net (code "65") (name "unconnected-(CAN2-Pad6)") (class "Default")
      (node (ref "CAN2") (pin "6") (pinfunction "6_6") (pintype "bidirectional"))
    )
    (net (code "66") (name "unconnected-(CAN2-Pad7)") (class "Default")
      (node (ref "CAN2") (pin "7") (pinfunction "7_7") (pintype "bidirectional"))
    )
    (net (code "67") (name "unconnected-(CAN2-Pad8)") (class "Default")
      (node (ref "CAN2") (pin "8") (pinfunction "8_8") (pintype "bidirectional"))
    )
    (net (code "68") (name "unconnected-(CAN2-Pad9)") (class "Default")
      (node (ref "CAN2") (pin "9") (pinfunction "9_9") (pintype "bidirectional"))
    )
    (net (code "69") (name "unconnected-(CAN2-PadMH1)") (class "Default")
      (node (ref "CAN2") (pin "MH1") (pinfunction "MH1_MH1") (pintype "bidirectional"))
    )
    (net (code "70") (name "unconnected-(CAN2-PadMH2)") (class "Default")
      (node (ref "CAN2") (pin "MH2") (pinfunction "MH2_MH2") (pintype "bidirectional"))
    )
    (net (code "71") (name "unconnected-(IC1A-Q2-Pad10)") (class "Default")
      (node (ref "IC1") (pin "10") (pinfunction "Q2_10") (pintype "output"))
    )
    (net (code "72") (name "unconnected-(IC1A-Q3-Pad1)") (class "Default")
      (node (ref "IC1") (pin "1") (pinfunction "Q3_1") (pintype "output"))
    )
    (net (code "73") (name "unconnected-(IC4A-~{SHDN}-Pad5)") (class "Default")
      (node (ref "IC4") (pin "5") (pinfunction "~{SHDN}_5") (pintype "input"))
    )
    (net (code "74") (name "unconnected-(ISOMETER_I/O-Pad4)") (class "Default")
      (node (ref "ISOMETER_I/O") (pin "4") (pinfunction "4_4") (pintype "bidirectional"))
    )
    (net (code "75") (name "unconnected-(ISOMETER_I/O-Pad6)") (class "Default")
      (node (ref "ISOMETER_I/O") (pin "6") (pinfunction "6_6") (pintype "bidirectional"))
    )
    (net (code "76") (name "unconnected-(ISOMETER_I/O-Pad7)") (class "Default")
      (node (ref "ISOMETER_I/O") (pin "7") (pinfunction "7_7") (pintype "bidirectional"))
    )
    (net (code "77") (name "unconnected-(THERAL_EX_I/O-Pad7)") (class "Default")
      (node (ref "THERAL_EX_I/O") (pin "7") (pinfunction "7_7") (pintype "bidirectional"))
    )
    (net (code "78") (name "unconnected-(WIFI_I/O-Pad4)") (class "Default")
      (node (ref "WIFI_I/O") (pin "4") (pinfunction "4_4") (pintype "bidirectional"))
    )
    (net (code "79") (name "unconnected-(WIFI_I/O-Pad6)") (class "Default")
      (node (ref "WIFI_I/O") (pin "6") (pinfunction "6_6") (pintype "bidirectional"))
    )
    (net (code "80") (name "unconnected-(WIFI_I/O-Pad7)") (class "Default")
      (node (ref "WIFI_I/O") (pin "7") (pinfunction "7_7") (pintype "bidirectional"))
    )
  )
)
